# xxxled-a.net
KiCad netlist of a schematic drawn in EAGLE
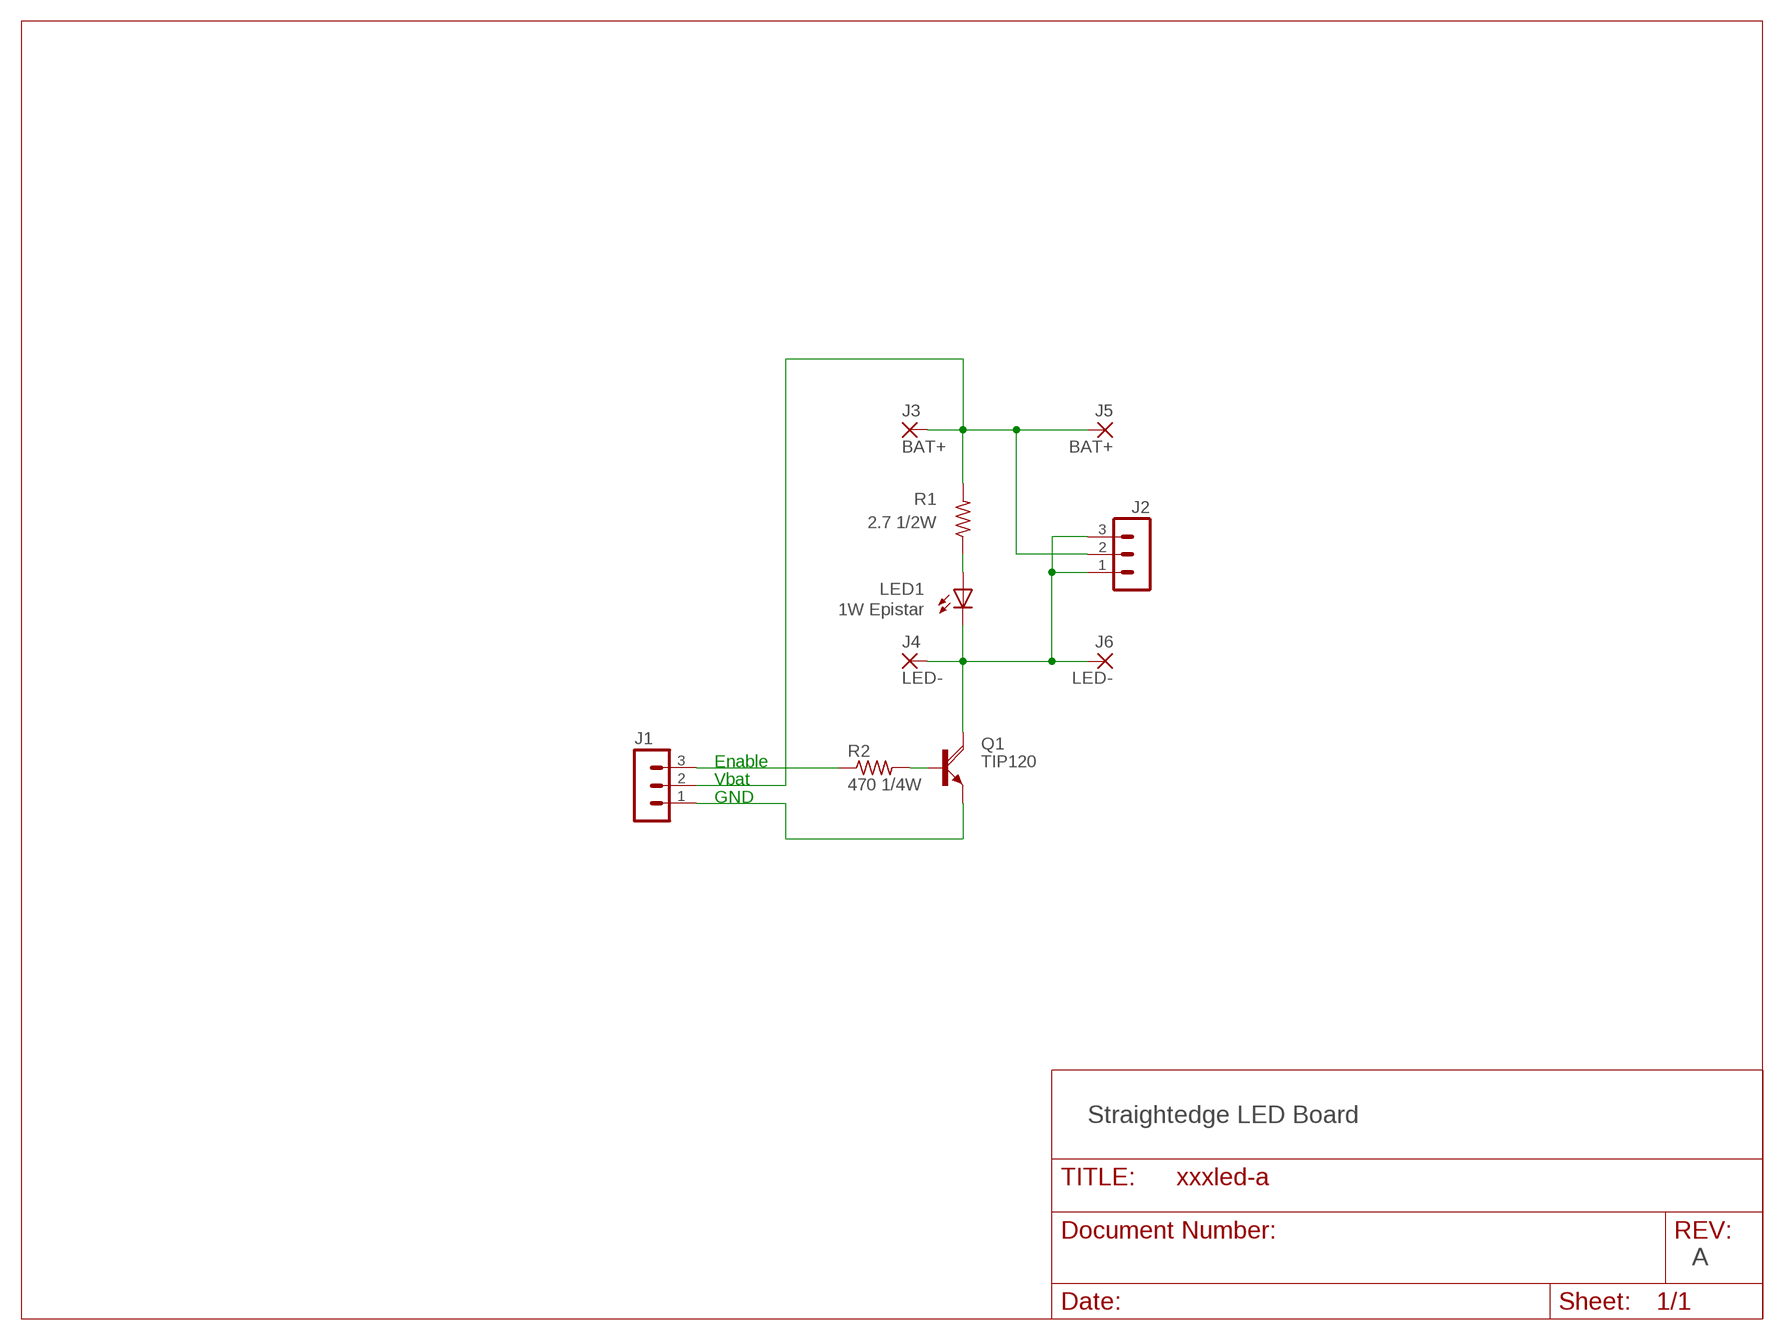
[diagram p0: schematic, sheet 1]

(export (version "E")
  (design (tool "Eeschema 10.0.6"))
  (components
    (comp (ref "J1")
      (value "MA03-1")
      (footprint "eagle-import:MA03-1")
      (libsource (lib "eagle-import") (part "MA03-1"))
    )
    (comp (ref "J2")
      (value "MA03-1")
      (footprint "eagle-import:MA03-1")
      (libsource (lib "eagle-import") (part "MA03-1"))
    )
    (comp (ref "J3")
      (value "BAT+")
      (footprint "eagle-import:2,54_1,1")
      (libsource (lib "eagle-import") (part "WIREPAD2,54/1,1"))
    )
    (comp (ref "J4")
      (value "LED-")
      (footprint "eagle-import:2,54_1,1")
      (libsource (lib "eagle-import") (part "WIREPAD2,54/1,1"))
    )
    (comp (ref "J5")
      (value "BAT+")
      (footprint "eagle-import:2,54_1,1")
      (libsource (lib "eagle-import") (part "WIREPAD2,54/1,1"))
    )
    (comp (ref "J6")
      (value "LED-")
      (footprint "eagle-import:2,54_1,1")
      (libsource (lib "eagle-import") (part "WIREPAD2,54/1,1"))
    )
    (comp (ref "LED1")
      (value "1W Epistar")
      (footprint "eagle-import:POWER_LED_EDGE")
      (libsource (lib "eagle-import") (part "W49180EDGE"))
    )
    (comp (ref "Q1")
      (value "TIP120")
      (footprint "eagle-import:TO220AH")
      (libsource (lib "eagle-import") (part "TIP120"))
    )
    (comp (ref "R1")
      (value "2.7 1/2W")
      (footprint "eagle-import:0309_12")
      (libsource (lib "eagle-import") (part "R-US_0309/12"))
    )
    (comp (ref "R2")
      (value "470 1/4W")
      (footprint "eagle-import:0207_10")
      (libsource (lib "eagle-import") (part "R-US_0207/10"))
    )
  )
  (nets
    (net (code "1") (name "Net-(J1-Pad1)") (class "Default")
      (node (ref "J1") (pin "1") (pinfunction "1_1") (pintype "passive"))
      (node (ref "Q1") (pin "E") (pinfunction "E_E") (pintype "passive"))
    )
    (net (code "2") (name "Net-(J1-Pad3)") (class "Default")
      (node (ref "J1") (pin "3") (pinfunction "3_3") (pintype "passive"))
      (node (ref "R2") (pin "1") (pinfunction "1_1") (pintype "passive"))
    )
    (net (code "3") (name "Net-(J3-P)") (class "Default")
      (node (ref "J1") (pin "2") (pinfunction "2_2") (pintype "passive"))
      (node (ref "J2") (pin "2") (pinfunction "2_2") (pintype "passive"))
      (node (ref "J3") (pin "1") (pinfunction "P_1") (pintype "passive"))
      (node (ref "J5") (pin "1") (pinfunction "P_1") (pintype "passive"))
      (node (ref "R1") (pin "2") (pinfunction "2_2") (pintype "passive"))
    )
    (net (code "4") (name "Net-(J4-P)") (class "Default")
      (node (ref "J2") (pin "1") (pinfunction "1_1") (pintype "passive"))
      (node (ref "J2") (pin "3") (pinfunction "3_3") (pintype "passive"))
      (node (ref "J4") (pin "1") (pinfunction "P_1") (pintype "passive"))
      (node (ref "J6") (pin "1") (pinfunction "P_1") (pintype "passive"))
      (node (ref "LED1") (pin "P$C") (pinfunction "C_P$C") (pintype "passive"))
      (node (ref "Q1") (pin "C") (pinfunction "C_C") (pintype "passive"))
    )
    (net (code "5") (name "Net-(LED1-A)") (class "Default")
      (node (ref "LED1") (pin "P$A") (pinfunction "A_P$A") (pintype "passive"))
      (node (ref "R1") (pin "1") (pinfunction "1_1") (pintype "passive"))
    )
    (net (code "6") (name "Net-(Q1-PadB)") (class "Default")
      (node (ref "Q1") (pin "B") (pinfunction "B_B") (pintype "passive"))
      (node (ref "R2") (pin "2") (pinfunction "2_2") (pintype "passive"))
    )
  )
)
